# ProPrj_LM324_TDA2030A.net
KiCad netlist of a schematic drawn in EasyEDA Pro
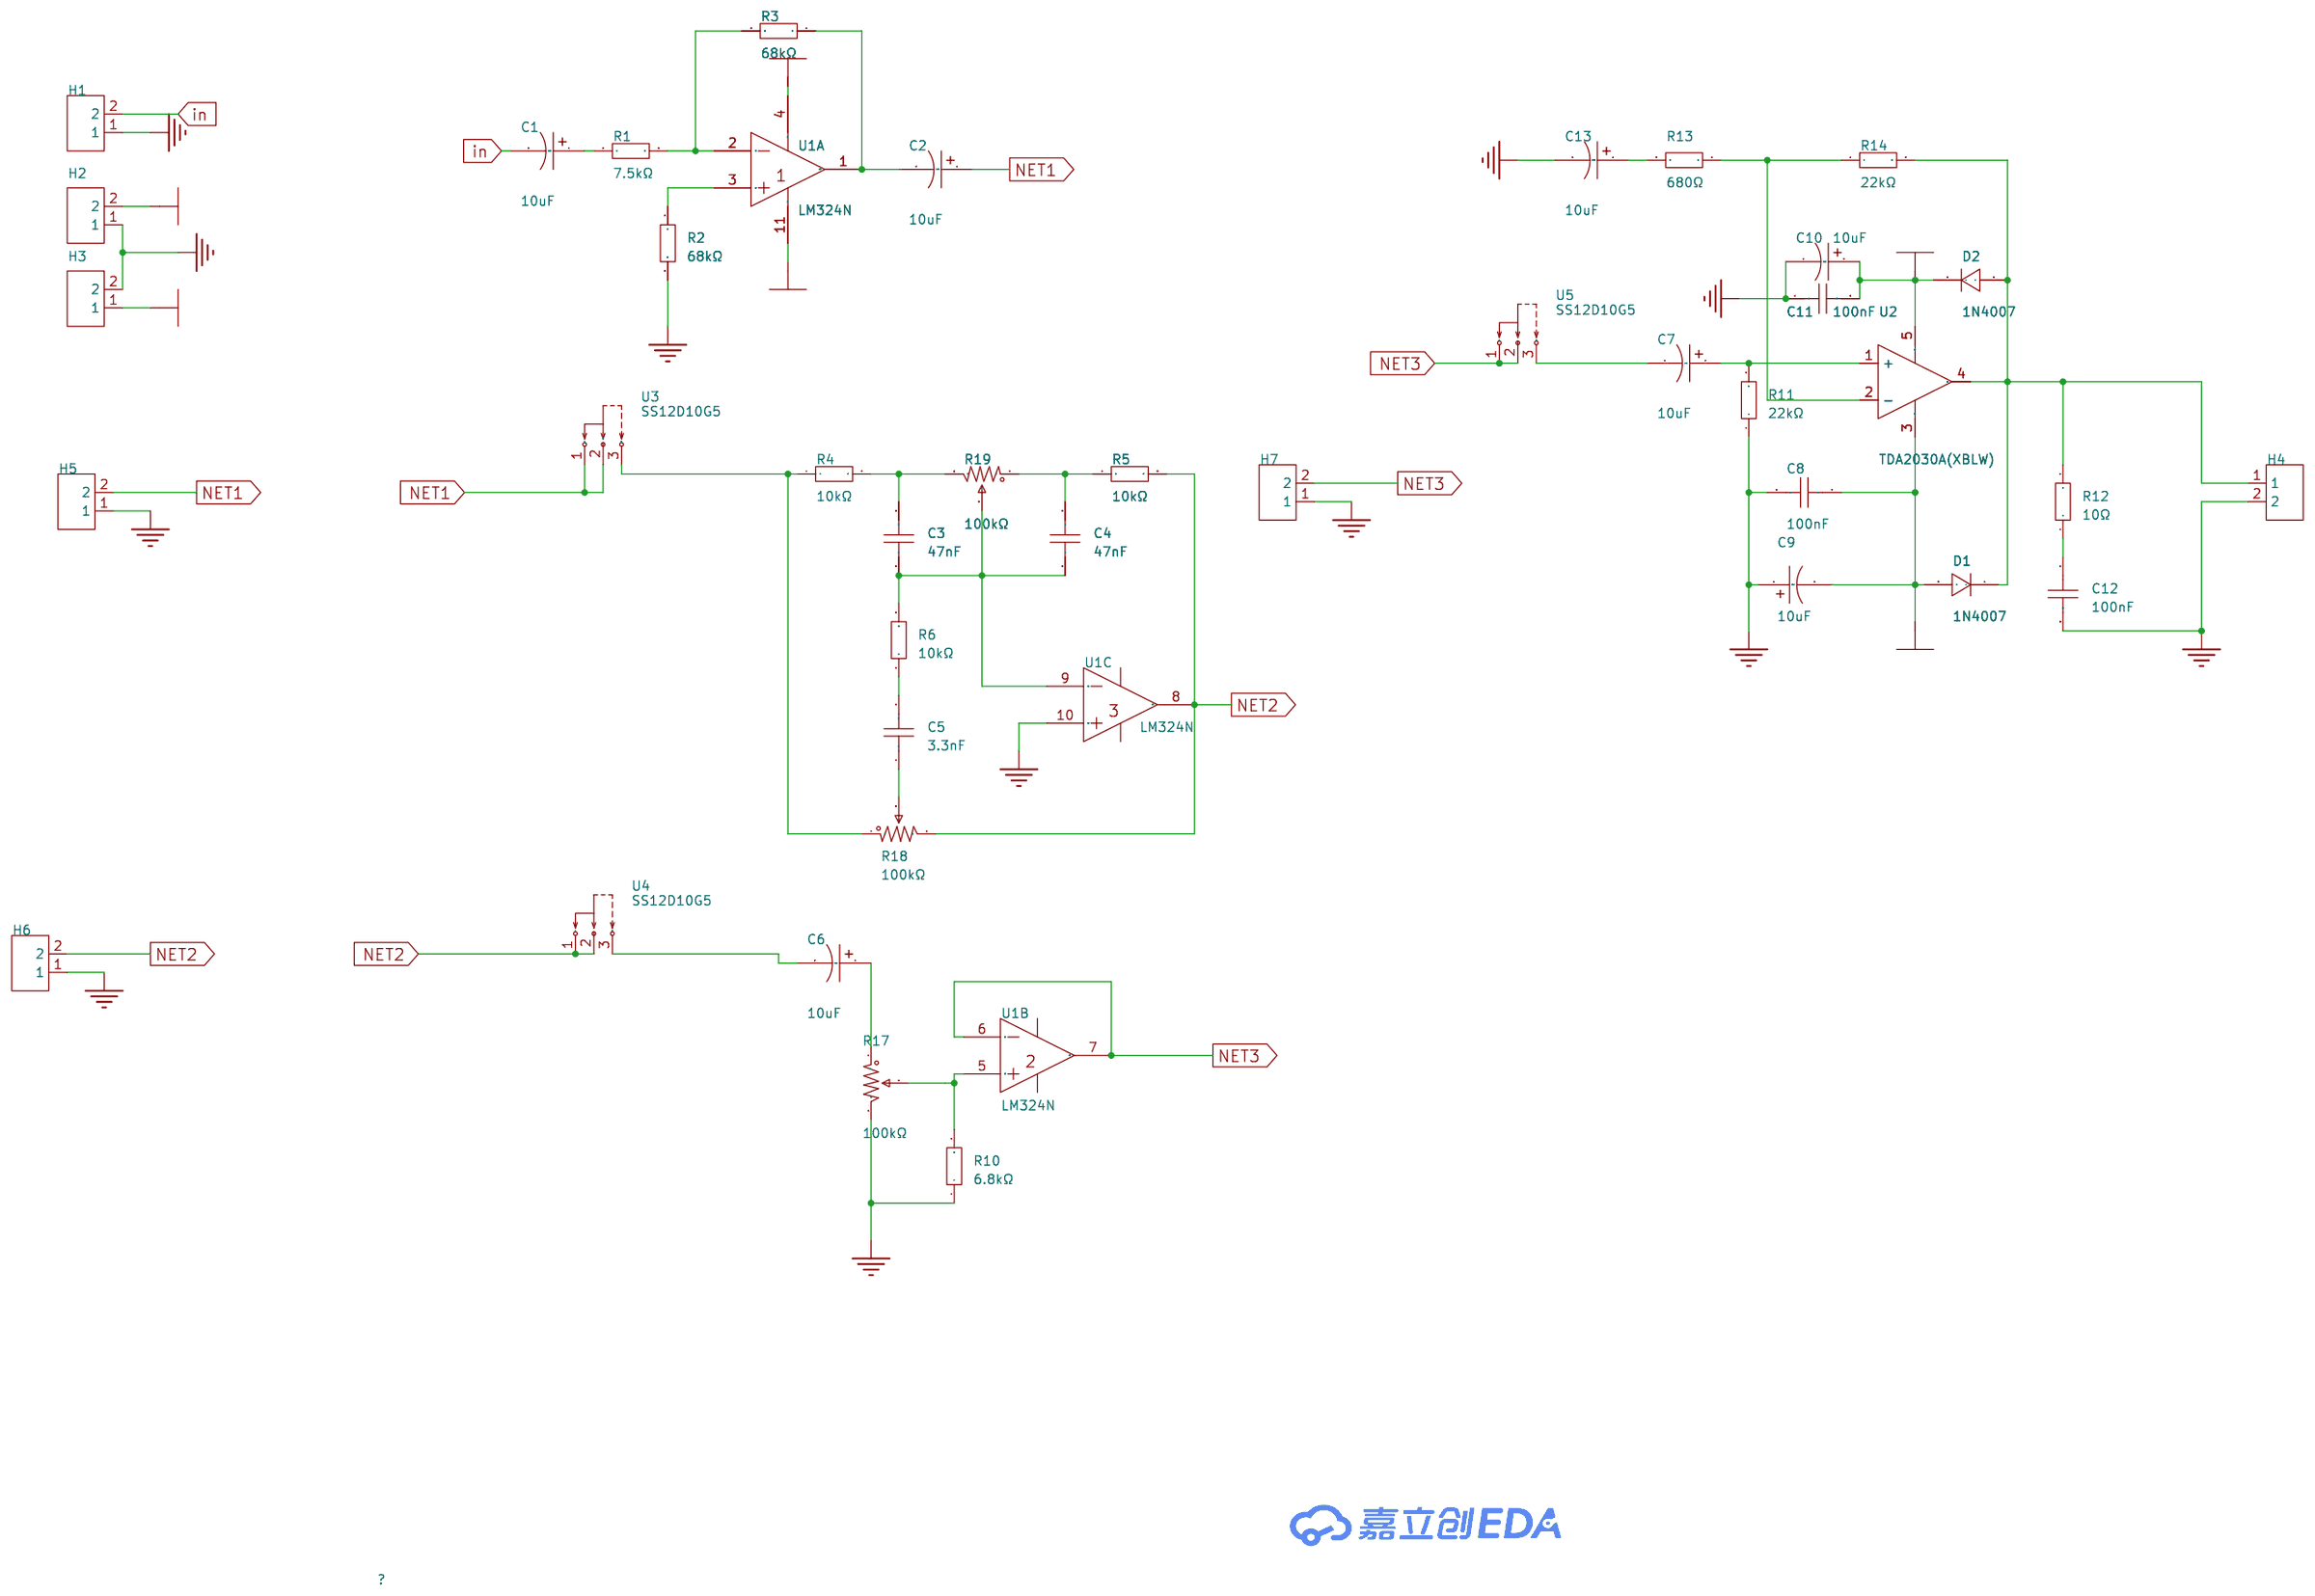
[diagram p0: schematic sheet]

(export (version "E")
  (design (tool "Eeschema 10.0.6"))
  (components
    (comp (ref "C1")
      (value "10uF")
      (footprint "easyedapro:CAP-SMD_L2.0-W1.3-FD")
      (description "容值:10uF;精度:±20%;额定电压:6.3V;等效串联电阻:500mΩ@100kHz;工作温度:-55°C~+105°C;")
      (fields (field (name "Manufacturer Part") "ERS1HM100D11OT") (field (name "Manufacturer") "AISHI(艾华集团)"))
      (libsource (lib "easyedapro") (part "TCJR106M006R0500E"))
    )
    (comp (ref "C2")
      (value "10uF")
      (footprint "easyedapro:CAP-SMD_L2.0-W1.3-FD")
      (description "容值:10uF;精度:±20%;额定电压:6.3V;等效串联电阻:500mΩ@100kHz;工作温度:-55°C~+105°C;")
      (fields (field (name "Manufacturer Part") "ERS1HM100D11OT") (field (name "Manufacturer") "AISHI(艾华集团)"))
      (libsource (lib "easyedapro") (part "TCJR106M006R0500E"))
    )
    (comp (ref "C3")
      (value "47nF")
      (footprint "easyedapro:C0603")
      (fields
        (field (name "Manufacturer Part") "CD1H473KC9BER1E100")
        (field (name "Manufacturer") "Dersonic(德尔创)")
      )
      (libsource (lib "easyedapro") (part "CapAcitance"))
    )
    (comp (ref "C4")
      (value "47nF")
      (footprint "easyedapro:C0603")
      (fields
        (field (name "Manufacturer Part") "CD1H473KC9BER1E100")
        (field (name "Manufacturer") "Dersonic(德尔创)")
      )
      (libsource (lib "easyedapro") (part "CapAcitance"))
    )
    (comp (ref "C5")
      (value "3.3nF")
      (footprint "easyedapro:C0603")
      (fields (field (name "Manufacturer Part") "CT4-0805B332K500F3") (field (name "Manufacturer") "FH(风华)"))
      (libsource (lib "easyedapro") (part "CapAcitance"))
    )
    (comp (ref "C6")
      (value "10uF")
      (footprint "easyedapro:CAP-SMD_L2.0-W1.3-FD")
      (description "容值:10uF;精度:±20%;额定电压:6.3V;等效串联电阻:500mΩ@100kHz;工作温度:-55°C~+105°C;")
      (fields (field (name "Manufacturer Part") "ERS1HM100D11OT") (field (name "Manufacturer") "AISHI(艾华集团)"))
      (libsource (lib "easyedapro") (part "TCJR106M006R0500E"))
    )
    (comp (ref "C7")
      (value "10uF")
      (footprint "easyedapro:CAP-SMD_L2.0-W1.3-FD")
      (description "容值:10uF;精度:±20%;额定电压:6.3V;等效串联电阻:500mΩ@100kHz;工作温度:-55°C~+105°C;")
      (fields (field (name "Manufacturer Part") "ERS1HM100D11OT") (field (name "Manufacturer") "AISHI(艾华集团)"))
      (libsource (lib "easyedapro") (part "TCJR106M006R0500E"))
    )
    (comp (ref "C8")
      (value "100nF")
      (footprint "easyedapro:C0603")
      (fields (field (name "Manufacturer Part") "178MU0013") (field (name "Manufacturer") "KNSCHA(科尼盛)"))
      (libsource (lib "easyedapro") (part "CapAcitance"))
    )
    (comp (ref "C9")
      (value "10uF")
      (footprint "easyedapro:CAP-SMD_L2.0-W1.3-FD")
      (description "容值:10uF;精度:±20%;额定电压:6.3V;等效串联电阻:500mΩ@100kHz;工作温度:-55°C~+105°C;")
      (fields (field (name "Manufacturer Part") "ERS1HM100D11OT") (field (name "Manufacturer") "AISHI(艾华集团)"))
      (libsource (lib "easyedapro") (part "TCJR106M006R0500E"))
    )
    (comp (ref "C10")
      (value "10uF")
      (footprint "easyedapro:CAP-SMD_L2.0-W1.3-FD")
      (description "容值:10uF;精度:±20%;额定电压:6.3V;等效串联电阻:500mΩ@100kHz;工作温度:-55°C~+105°C;")
      (fields (field (name "Manufacturer Part") "ERS1HM100D11OT") (field (name "Manufacturer") "AISHI(艾华集团)"))
      (libsource (lib "easyedapro") (part "TCJR106M006R0500E"))
    )
    (comp (ref "C11")
      (value "100nF")
      (footprint "easyedapro:C0603")
      (fields (field (name "Manufacturer Part") "178MU0013") (field (name "Manufacturer") "KNSCHA(科尼盛)"))
      (libsource (lib "easyedapro") (part "CapAcitance"))
    )
    (comp (ref "C12")
      (value "100nF")
      (footprint "easyedapro:C0603")
      (fields (field (name "Manufacturer Part") "178MU0013") (field (name "Manufacturer") "KNSCHA(科尼盛)"))
      (libsource (lib "easyedapro") (part "CapAcitance"))
    )
    (comp (ref "C13")
      (value "10uF")
      (footprint "easyedapro:CAP-SMD_L2.0-W1.3-FD")
      (description "容值:10uF;精度:±20%;额定电压:6.3V;等效串联电阻:500mΩ@100kHz;工作温度:-55°C~+105°C;")
      (fields (field (name "Manufacturer Part") "ERS1HM100D11OT") (field (name "Manufacturer") "AISHI(艾华集团)"))
      (libsource (lib "easyedapro") (part "TCJR106M006R0500E"))
    )
    (comp (ref "D1")
      (value "1N4007")
      (footprint "easyedapro:DO-41_BD2.4-L4.7-P8.70-D0.9-RD")
      (description "二极管配置:独立式;直流反向耐压(Vr):1kV;平均整流电流(Io):1A;正向压降(Vf):1V@1A;反向电流(Ir):5μA@1kV;")
      (fields (field (name "Manufacturer") "PINGWEI(平伟)"))
      (libsource (lib "easyedapro") (part "1N4007_C360242"))
    )
    (comp (ref "D2")
      (value "1N4007")
      (footprint "easyedapro:DO-41_BD2.4-L4.7-P8.70-D0.9-RD")
      (description "二极管配置:独立式;直流反向耐压(Vr):1kV;平均整流电流(Io):1A;正向压降(Vf):1V@1A;反向电流(Ir):5μA@1kV;")
      (fields (field (name "Manufacturer") "PINGWEI(平伟)"))
      (libsource (lib "easyedapro") (part "1N4007_C360242"))
    )
    (comp (ref "H1")
      (value "PZ254V-11-02P")
      (footprint "easyedapro:HDR-TH_2P-P2.54-V-M")
      (fields (field (name "Manufacturer") "XFCN(兴飞)"))
      (libsource (lib "easyedapro") (part "PZ254V-11-02P"))
    )
    (comp (ref "H2")
      (value "PZ254V-11-02P")
      (footprint "easyedapro:HDR-TH_2P-P2.54-V-M")
      (fields (field (name "Manufacturer") "XFCN(兴飞)"))
      (libsource (lib "easyedapro") (part "PZ254V-11-02P"))
    )
    (comp (ref "H3")
      (value "PZ254V-11-02P")
      (footprint "easyedapro:HDR-TH_2P-P2.54-V-M")
      (fields (field (name "Manufacturer") "XFCN(兴飞)"))
      (libsource (lib "easyedapro") (part "PZ254V-11-02P"))
    )
    (comp (ref "H4")
      (value "PZ254V-11-02P")
      (footprint "easyedapro:HDR-TH_2P-P2.54-V-M")
      (fields (field (name "Manufacturer") "XFCN(兴飞)"))
      (libsource (lib "easyedapro") (part "PZ254V-11-02P"))
    )
    (comp (ref "H5")
      (value "PZ254V-11-02P")
      (footprint "easyedapro:HDR-TH_2P-P2.54-V-M")
      (fields (field (name "Manufacturer") "XFCN(兴飞)"))
      (libsource (lib "easyedapro") (part "PZ254V-11-02P"))
    )
    (comp (ref "H6")
      (value "PZ254V-11-02P")
      (footprint "easyedapro:HDR-TH_2P-P2.54-V-M")
      (fields (field (name "Manufacturer") "XFCN(兴飞)"))
      (libsource (lib "easyedapro") (part "PZ254V-11-02P"))
    )
    (comp (ref "H7")
      (value "PZ254V-11-02P")
      (footprint "easyedapro:HDR-TH_2P-P2.54-V-M")
      (fields (field (name "Manufacturer") "XFCN(兴飞)"))
      (libsource (lib "easyedapro") (part "PZ254V-11-02P"))
    )
    (comp (ref "R1")
      (value "7.5kΩ")
      (footprint "easyedapro:R0603")
      (fields (field (name "Manufacturer Part") "MF1/8W-7K5±1%-ST52") (field (name "Manufacturer") "VO(翔胜)"))
      (libsource (lib "easyedapro") (part "电阻"))
    )
    (comp (ref "R2")
      (value "68kΩ")
      (footprint "easyedapro:R0603")
      (fields (field (name "Manufacturer Part") "MF1/4W-68K ±1%-ST52") (field (name "Manufacturer") "VO(翔胜)"))
      (libsource (lib "easyedapro") (part "电阻"))
    )
    (comp (ref "R3")
      (value "68kΩ")
      (footprint "easyedapro:R0603")
      (fields (field (name "Manufacturer Part") "MF1/4W-68K ±1%-ST52") (field (name "Manufacturer") "VO(翔胜)"))
      (libsource (lib "easyedapro") (part "电阻"))
    )
    (comp (ref "R4")
      (value "10kΩ")
      (footprint "easyedapro:R0603")
      (fields (field (name "Manufacturer Part") "MF1/4W-10K±1%-ST52") (field (name "Manufacturer") "VO(翔胜)"))
      (libsource (lib "easyedapro") (part "电阻"))
    )
    (comp (ref "R5")
      (value "10kΩ")
      (footprint "easyedapro:R0603")
      (fields (field (name "Manufacturer Part") "MF1/4W-10K±1%-ST52") (field (name "Manufacturer") "VO(翔胜)"))
      (libsource (lib "easyedapro") (part "电阻"))
    )
    (comp (ref "R6")
      (value "10kΩ")
      (footprint "easyedapro:R0603")
      (fields (field (name "Manufacturer Part") "MF1/4W-10K±1%-ST52") (field (name "Manufacturer") "VO(翔胜)"))
      (libsource (lib "easyedapro") (part "电阻"))
    )
    (comp (ref "R10")
      (value "6.8kΩ")
      (footprint "easyedapro:R0603")
      (fields (field (name "Manufacturer Part") "CR1/4W-6K8±5%-ST26") (field (name "Manufacturer") "VO(翔胜)"))
      (libsource (lib "easyedapro") (part "电阻"))
    )
    (comp (ref "R11")
      (value "22kΩ")
      (footprint "easyedapro:R0603")
      (fields (field (name "Manufacturer Part") "MF1/8W ±1% 22K OTB5") (field (name "Manufacturer") "VO(翔胜)"))
      (libsource (lib "easyedapro") (part "电阻"))
    )
    (comp (ref "R12")
      (value "10Ω")
      (footprint "easyedapro:R0603")
      (fields (field (name "Manufacturer Part") "MF1/8W-10Ω±1%-OT52") (field (name "Manufacturer") "VO(翔胜)"))
      (libsource (lib "easyedapro") (part "电阻"))
    )
    (comp (ref "R13")
      (value "680Ω")
      (footprint "easyedapro:R0603")
      (fields (field (name "Manufacturer Part") "MF1/8W-680Ω±1%-ST52") (field (name "Manufacturer") "VO(翔胜)"))
      (libsource (lib "easyedapro") (part "电阻"))
    )
    (comp (ref "R14")
      (value "22kΩ")
      (footprint "easyedapro:R0603")
      (fields (field (name "Manufacturer Part") "MF1/8W ±1% 22K OTB5") (field (name "Manufacturer") "VO(翔胜)"))
      (libsource (lib "easyedapro") (part "电阻"))
    )
    (comp (ref "R17")
      (value "100kΩ")
      (footprint "easyedapro:RES-ADJ-SMD_RM065-V1")
      (description "阻值:10kΩ;精度:±25%;功率:100mW;")
      (fields (field (name "Manufacturer Part") "3362P-1-104") (field (name "Manufacturer") "BOCHEN(博晨)"))
      (libsource (lib "easyedapro") (part "RM065-103(10K)"))
    )
    (comp (ref "R18")
      (value "100kΩ")
      (footprint "easyedapro:RES-ADJ-SMD_RM065-V1")
      (description "阻值:10kΩ;精度:±25%;功率:100mW;")
      (fields (field (name "Manufacturer Part") "3362P-1-104") (field (name "Manufacturer") "BOCHEN(博晨)"))
      (libsource (lib "easyedapro") (part "RM065-103(10K)"))
    )
    (comp (ref "R19")
      (value "100kΩ")
      (footprint "easyedapro:RES-ADJ-SMD_RM065-V1")
      (description "阻值:10kΩ;精度:±25%;功率:100mW;")
      (fields (field (name "Manufacturer Part") "3362P-1-104") (field (name "Manufacturer") "BOCHEN(博晨)"))
      (libsource (lib "easyedapro") (part "RM065-103(10K)"))
    )
    (comp (ref "U1")
      (value "LM324N")
      (footprint "easyedapro:DIP-14_L19.4-W6.4-P2.54-LS7.6-BL")
      (description "运放类型:-;放大器组数:-;增益带宽积（GBP）:-;压摆率（SR）:-;电源电压:-;各通道供电电流:-;")
      (fields (field (name "Manufacturer") "HGSEMI(华冠)"))
      (libsource (lib "easyedapro") (part "LM324N_C725320"))
    )
    (comp (ref "U2")
      (value "TDA2030A(XBLW)")
      (footprint "easyedapro:TO-220-5_L10.5-W15.5-P1.70-TL")
      (description "音频功率放大器的类型:Class AB;输出类型:1-Channel (Mono);输出功率:12W x 1 @ 8Ω;工作电压:±6V ~ 22V;")
      (fields (field (name "Manufacturer") "XBLW(芯伯乐)"))
      (libsource (lib "easyedapro") (part "TDA2030AL-TB5-T"))
    )
    (comp (ref "U3")
      (value "SS12D10G5")
      (footprint "easyedapro:SW-TH_SHOU-HAN_SS12D10G4")
      (description "电路结构:单刀双掷;安装方式:直插;额定电流(DC):2A;额定电压(DC):125V;机械寿命:3千次;")
      (fields (field (name "Manufacturer") "SHOU HAN(首韩)"))
      (libsource (lib "easyedapro") (part "SS12D10G5"))
    )
    (comp (ref "U4")
      (value "SS12D10G5")
      (footprint "easyedapro:SW-TH_SHOU-HAN_SS12D10G4")
      (description "电路结构:单刀双掷;安装方式:直插;额定电流(DC):2A;额定电压(DC):125V;机械寿命:3千次;")
      (fields (field (name "Manufacturer") "SHOU HAN(首韩)"))
      (libsource (lib "easyedapro") (part "SS12D10G5"))
    )
    (comp (ref "U5")
      (value "SS12D10G5")
      (footprint "easyedapro:SW-TH_SHOU-HAN_SS12D10G4")
      (description "电路结构:单刀双掷;安装方式:直插;额定电流(DC):2A;额定电压(DC):125V;机械寿命:3千次;")
      (fields (field (name "Manufacturer") "SHOU HAN(首韩)"))
      (libsource (lib "easyedapro") (part "SS12D10G5"))
    )
  )
  (nets
    (net (code "1") (name "+VCC") (class "Default")
      (node (ref "C10") (pin "1") (pinfunction "1_1") (pintype "input"))
      (node (ref "C11") (pin "2") (pinfunction "2_2") (pintype "input"))
      (node (ref "D2") (pin "1") (pinfunction "-_1") (pintype "input"))
      (node (ref "H2") (pin "2") (pinfunction "2_2") (pintype "unspecified"))
      (node (ref "U1") (pin "4") (pinfunction "VCC_4") (pintype "input"))
      (node (ref "U2") (pin "5") (pinfunction "VCC+_5") (pintype "input"))
    )
    (net (code "2") (name "-VCC") (class "Default")
      (node (ref "C8") (pin "1") (pinfunction "1_1") (pintype "input"))
      (node (ref "C9") (pin "2") (pinfunction "2_2") (pintype "input"))
      (node (ref "D1") (pin "2") (pinfunction "+_2") (pintype "input"))
      (node (ref "H3") (pin "1") (pinfunction "1_1") (pintype "unspecified"))
      (node (ref "U1") (pin "11") (pinfunction "GND_11") (pintype "input"))
      (node (ref "U2") (pin "3") (pinfunction "GND_3") (pintype "input"))
    )
    (net (code "3") (name "GND") (class "Default")
      (node (ref "C10") (pin "2") (pinfunction "2_2") (pintype "input"))
      (node (ref "C11") (pin "1") (pinfunction "1_1") (pintype "input"))
      (node (ref "C12") (pin "2") (pinfunction "2_2") (pintype "input"))
      (node (ref "C13") (pin "2") (pinfunction "2_2") (pintype "input"))
      (node (ref "C8") (pin "2") (pinfunction "2_2") (pintype "input"))
      (node (ref "C9") (pin "1") (pinfunction "1_1") (pintype "input"))
      (node (ref "H1") (pin "1") (pinfunction "1_1") (pintype "unspecified"))
      (node (ref "H2") (pin "1") (pinfunction "1_1") (pintype "unspecified"))
      (node (ref "H3") (pin "2") (pinfunction "2_2") (pintype "unspecified"))
      (node (ref "H4") (pin "2") (pinfunction "2_2") (pintype "unspecified"))
      (node (ref "H5") (pin "1") (pinfunction "1_1") (pintype "unspecified"))
      (node (ref "H6") (pin "1") (pinfunction "1_1") (pintype "unspecified"))
      (node (ref "H7") (pin "1") (pinfunction "1_1") (pintype "unspecified"))
      (node (ref "R10") (pin "1") (pinfunction "1_1") (pintype "input"))
      (node (ref "R11") (pin "1") (pinfunction "1_1") (pintype "input"))
      (node (ref "R17") (pin "3") (pinfunction "3_3") (pintype "unspecified"))
      (node (ref "R2") (pin "2") (pinfunction "2_2") (pintype "input"))
      (node (ref "U1") (pin "10") (pinfunction "IN3+_10") (pintype "input"))
    )
    (net (code "4") (name "NET1") (class "Default")
      (node (ref "C2") (pin "1") (pinfunction "1_1") (pintype "input"))
      (node (ref "H5") (pin "2") (pinfunction "2_2") (pintype "unspecified"))
      (node (ref "U3") (pin "1") (pinfunction "1_1") (pintype "unspecified"))
      (node (ref "U3") (pin "2") (pinfunction "2_2") (pintype "unspecified"))
    )
    (net (code "5") (name "NET2") (class "Default")
      (node (ref "H6") (pin "2") (pinfunction "2_2") (pintype "unspecified"))
      (node (ref "R18") (pin "3") (pinfunction "3_3") (pintype "unspecified"))
      (node (ref "R5") (pin "2") (pinfunction "2_2") (pintype "input"))
      (node (ref "U1") (pin "8") (pinfunction "OUT3_8") (pintype "output"))
      (node (ref "U4") (pin "1") (pinfunction "1_1") (pintype "unspecified"))
      (node (ref "U4") (pin "2") (pinfunction "2_2") (pintype "unspecified"))
    )
    (net (code "6") (name "NET3") (class "Default")
      (node (ref "H7") (pin "2") (pinfunction "2_2") (pintype "unspecified"))
      (node (ref "U1") (pin "6") (pinfunction "IN2-_6") (pintype "input"))
      (node (ref "U1") (pin "7") (pinfunction "OUT2_7") (pintype "output"))
      (node (ref "U5") (pin "1") (pinfunction "1_1") (pintype "unspecified"))
      (node (ref "U5") (pin "2") (pinfunction "2_2") (pintype "unspecified"))
    )
    (net (code "7") (name "Net-(C1-Pad1)") (class "Default")
      (node (ref "C1") (pin "1") (pinfunction "1_1") (pintype "input"))
      (node (ref "R1") (pin "1") (pinfunction "1_1") (pintype "input"))
    )
    (net (code "8") (name "Net-(C3-Pad2)") (class "Default")
      (node (ref "C3") (pin "2") (pinfunction "2_2") (pintype "input"))
      (node (ref "R19") (pin "3") (pinfunction "3_3") (pintype "unspecified"))
      (node (ref "R4") (pin "2") (pinfunction "2_2") (pintype "input"))
    )
    (net (code "9") (name "Net-(C4-Pad2)") (class "Default")
      (node (ref "C4") (pin "2") (pinfunction "2_2") (pintype "input"))
      (node (ref "R19") (pin "1") (pinfunction "1_1") (pintype "unspecified"))
      (node (ref "R5") (pin "1") (pinfunction "1_1") (pintype "input"))
    )
    (net (code "10") (name "Net-(C5-Pad1)") (class "Default")
      (node (ref "C5") (pin "1") (pinfunction "1_1") (pintype "input"))
      (node (ref "R18") (pin "2") (pinfunction "2_2") (pintype "unspecified"))
    )
    (net (code "11") (name "Net-(C5-Pad2)") (class "Default")
      (node (ref "C5") (pin "2") (pinfunction "2_2") (pintype "input"))
      (node (ref "R6") (pin "1") (pinfunction "1_1") (pintype "input"))
    )
    (net (code "12") (name "Net-(C6-Pad1)") (class "Default")
      (node (ref "C6") (pin "1") (pinfunction "1_1") (pintype "input"))
      (node (ref "R17") (pin "1") (pinfunction "1_1") (pintype "unspecified"))
    )
    (net (code "13") (name "Net-(C6-Pad2)") (class "Default")
      (node (ref "C6") (pin "2") (pinfunction "2_2") (pintype "input"))
      (node (ref "U4") (pin "3") (pinfunction "3_3") (pintype "unspecified"))
    )
    (net (code "14") (name "Net-(C7-Pad2)") (class "Default")
      (node (ref "C7") (pin "2") (pinfunction "2_2") (pintype "input"))
      (node (ref "U5") (pin "3") (pinfunction "3_3") (pintype "unspecified"))
    )
    (net (code "15") (name "Net-(C12-Pad1)") (class "Default")
      (node (ref "C12") (pin "1") (pinfunction "1_1") (pintype "input"))
      (node (ref "R12") (pin "1") (pinfunction "1_1") (pintype "input"))
    )
    (net (code "16") (name "Net-(C13-Pad1)") (class "Default")
      (node (ref "C13") (pin "1") (pinfunction "1_1") (pintype "input"))
      (node (ref "R13") (pin "2") (pinfunction "2_2") (pintype "input"))
    )
    (net (code "17") (name "Net-(D1--)") (class "Default")
      (node (ref "D1") (pin "1") (pinfunction "-_1") (pintype "input"))
      (node (ref "D2") (pin "2") (pinfunction "+_2") (pintype "input"))
      (node (ref "H4") (pin "1") (pinfunction "1_1") (pintype "unspecified"))
      (node (ref "R12") (pin "2") (pinfunction "2_2") (pintype "input"))
      (node (ref "R14") (pin "2") (pinfunction "2_2") (pintype "input"))
      (node (ref "U2") (pin "4") (pinfunction "OUT_4") (pintype "input"))
    )
    (net (code "18") (name "Net-(R18-Pad1)") (class "Default")
      (node (ref "R18") (pin "1") (pinfunction "1_1") (pintype "unspecified"))
      (node (ref "R4") (pin "1") (pinfunction "1_1") (pintype "input"))
      (node (ref "U3") (pin "3") (pinfunction "3_3") (pintype "unspecified"))
    )
    (net (code "19") (name "Net-(U1A-IN1+)") (class "Default")
      (node (ref "R2") (pin "1") (pinfunction "1_1") (pintype "input"))
      (node (ref "U1") (pin "3") (pinfunction "IN1+_3") (pintype "input"))
    )
    (net (code "20") (name "Net-(U1A-IN1-)") (class "Default")
      (node (ref "R1") (pin "2") (pinfunction "2_2") (pintype "input"))
      (node (ref "R3") (pin "2") (pinfunction "2_2") (pintype "input"))
      (node (ref "U1") (pin "2") (pinfunction "IN1-_2") (pintype "input"))
    )
    (net (code "21") (name "Net-(U1A-OUT1)") (class "Default")
      (node (ref "C2") (pin "2") (pinfunction "2_2") (pintype "input"))
      (node (ref "R3") (pin "1") (pinfunction "1_1") (pintype "input"))
      (node (ref "U1") (pin "1") (pinfunction "OUT1_1") (pintype "output"))
    )
    (net (code "22") (name "Net-(U1B-IN2+)") (class "Default")
      (node (ref "R10") (pin "2") (pinfunction "2_2") (pintype "input"))
      (node (ref "R17") (pin "2") (pinfunction "2_2") (pintype "unspecified"))
      (node (ref "U1") (pin "5") (pinfunction "IN2+_5") (pintype "input"))
    )
    (net (code "23") (name "Net-(U1C-IN3-)") (class "Default")
      (node (ref "C3") (pin "1") (pinfunction "1_1") (pintype "input"))
      (node (ref "C4") (pin "1") (pinfunction "1_1") (pintype "input"))
      (node (ref "R19") (pin "2") (pinfunction "2_2") (pintype "unspecified"))
      (node (ref "R6") (pin "2") (pinfunction "2_2") (pintype "input"))
      (node (ref "U1") (pin "9") (pinfunction "IN3-_9") (pintype "input"))
    )
    (net (code "24") (name "Net-(U2-+)") (class "Default")
      (node (ref "C7") (pin "1") (pinfunction "1_1") (pintype "input"))
      (node (ref "R11") (pin "2") (pinfunction "2_2") (pintype "input"))
      (node (ref "U2") (pin "1") (pinfunction "+_1") (pintype "input"))
    )
    (net (code "25") (name "Net-(U2--)") (class "Default")
      (node (ref "R13") (pin "1") (pinfunction "1_1") (pintype "input"))
      (node (ref "R14") (pin "1") (pinfunction "1_1") (pintype "input"))
      (node (ref "U2") (pin "2") (pinfunction "-_2") (pintype "input"))
    )
    (net (code "26") (name "in") (class "Default")
      (node (ref "C1") (pin "2") (pinfunction "2_2") (pintype "input"))
      (node (ref "H1") (pin "2") (pinfunction "2_2") (pintype "unspecified"))
    )
  )
)
